# HMC1001_FreeSize_V1_0.net
KiCad netlist of a schematic drawn in Altium Designer
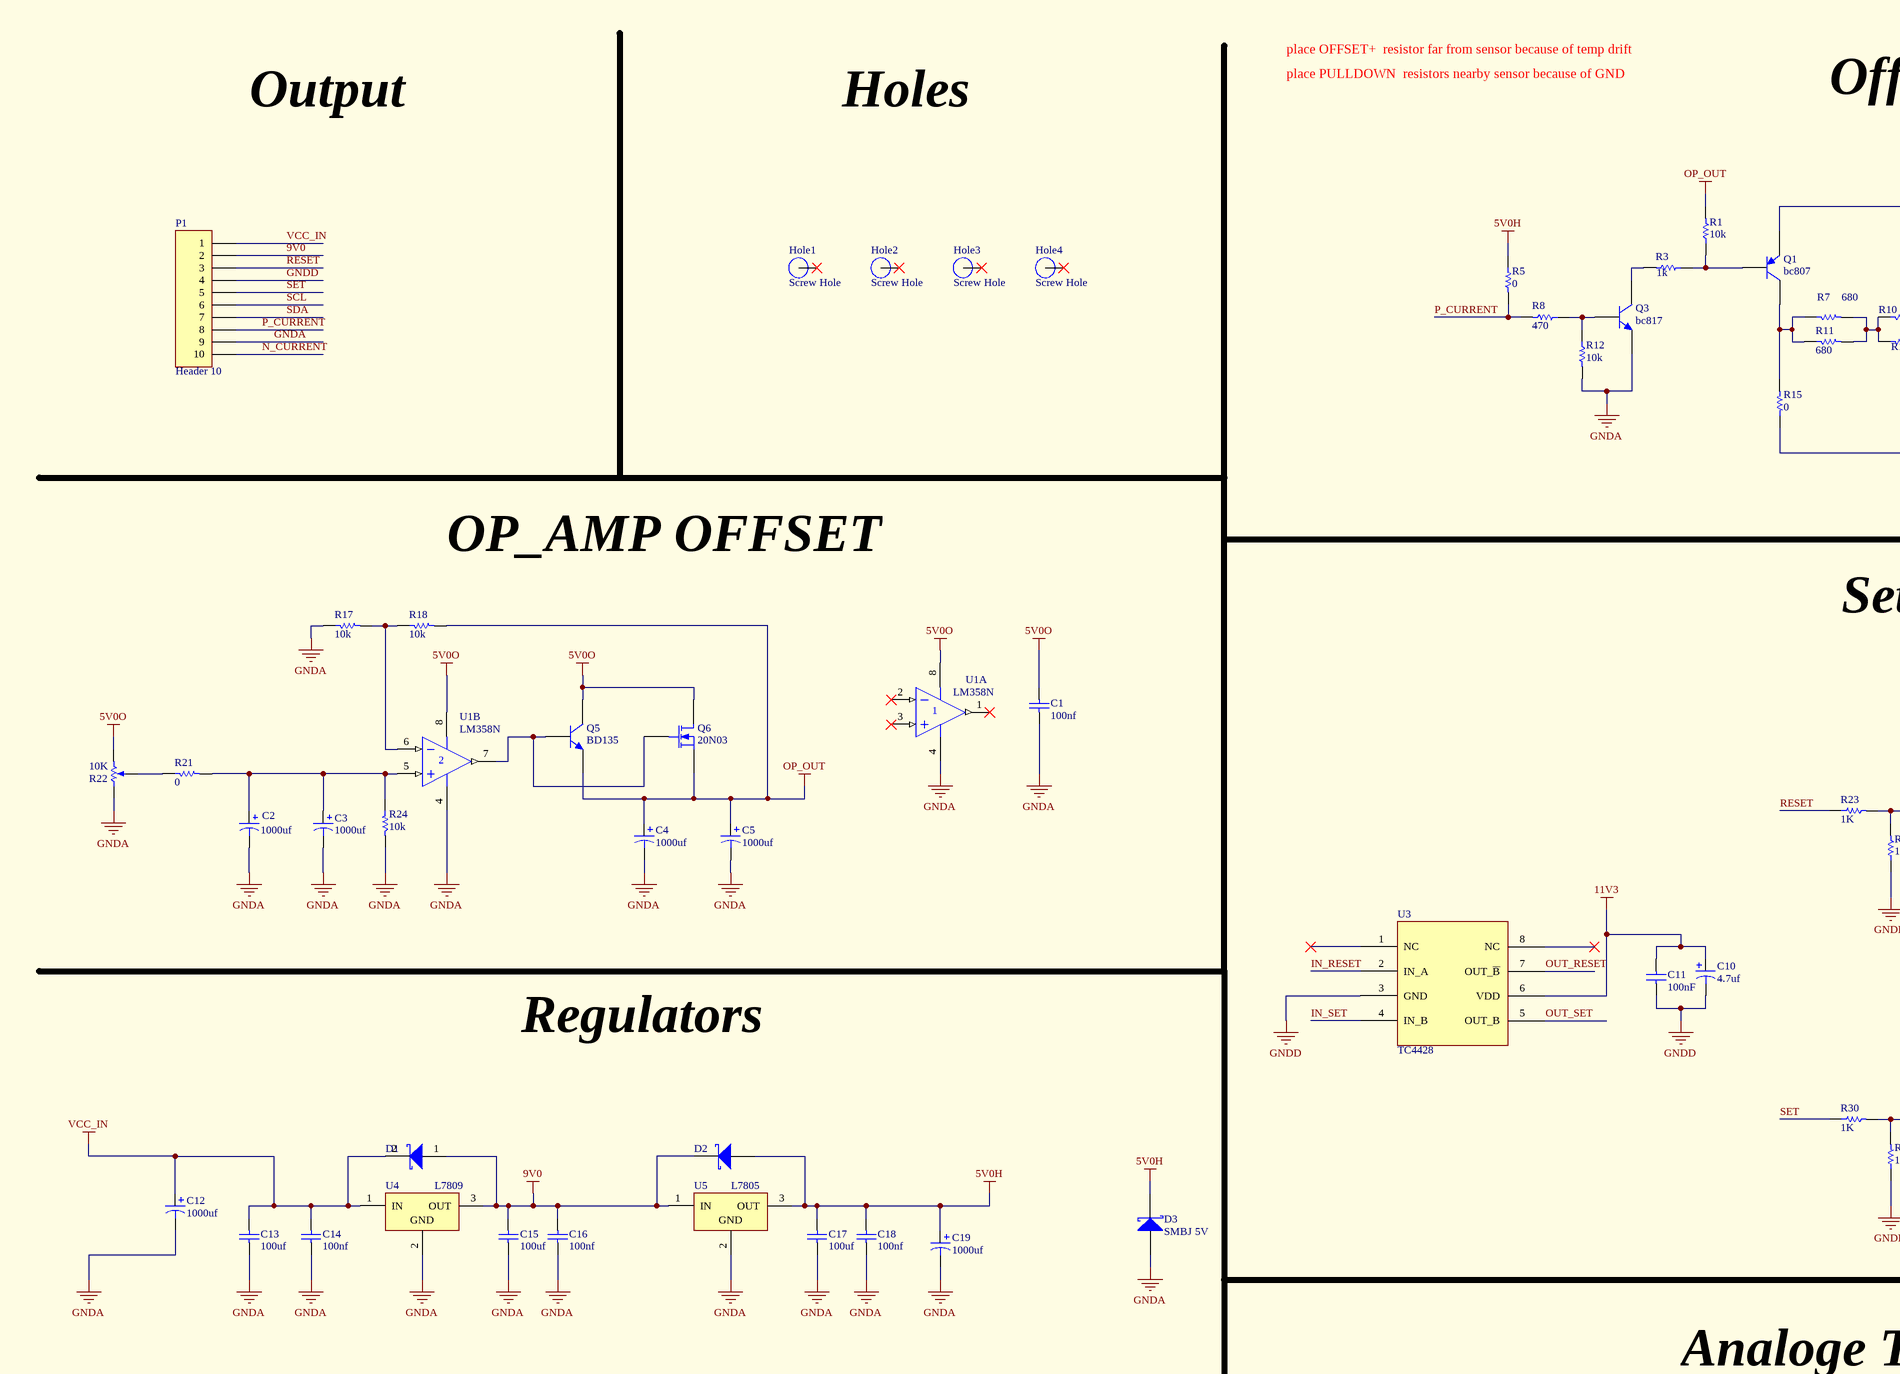
[diagram p0: HMC1001_FreeSize_V1_0.SchDoc, top left]
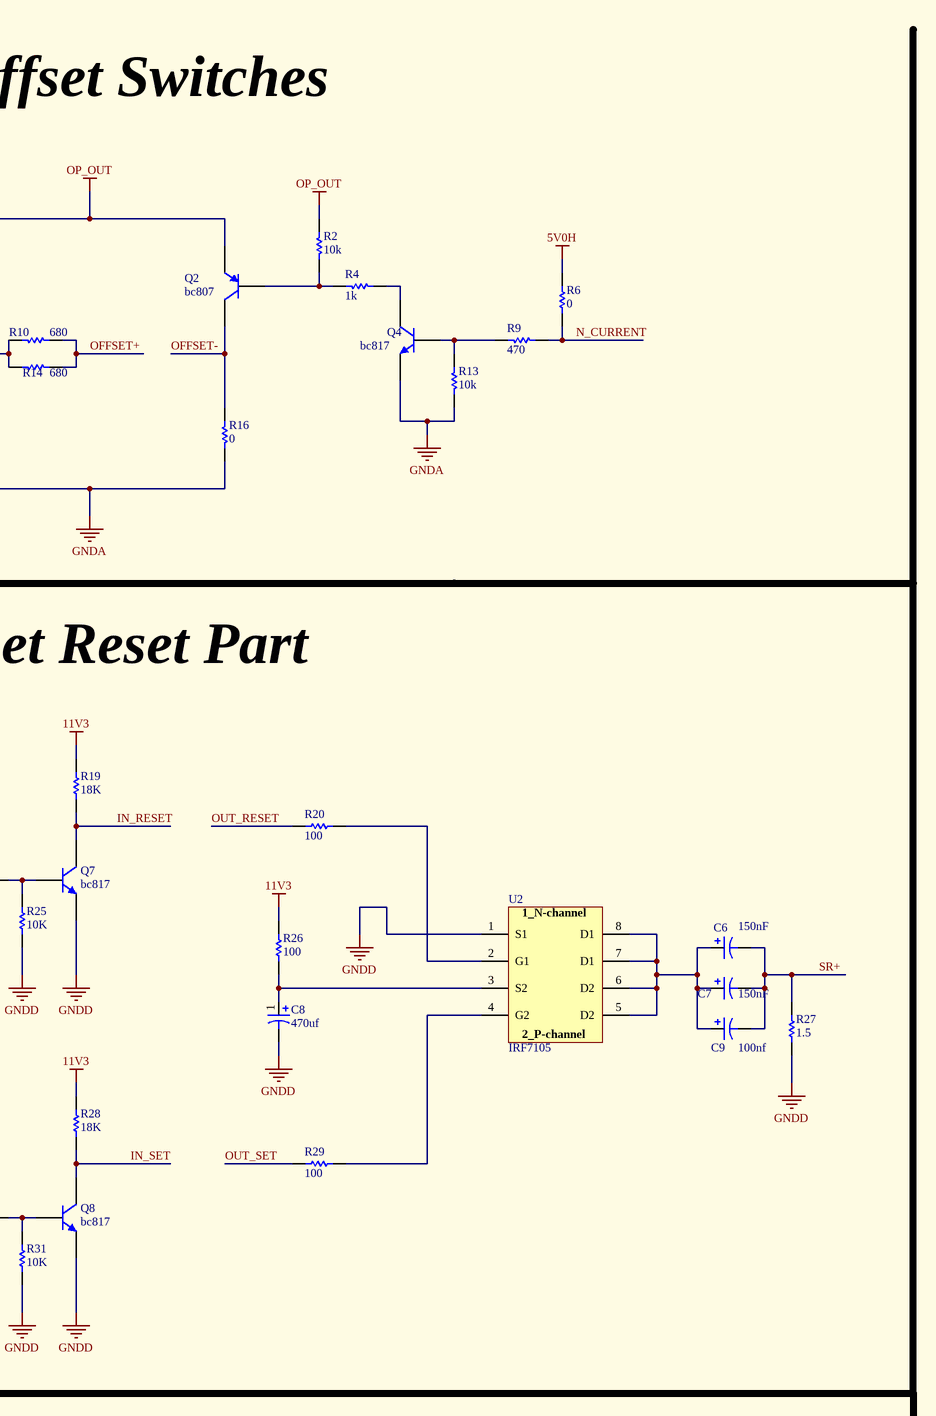
[diagram p1: HMC1001_FreeSize_V1_0.SchDoc, top right]
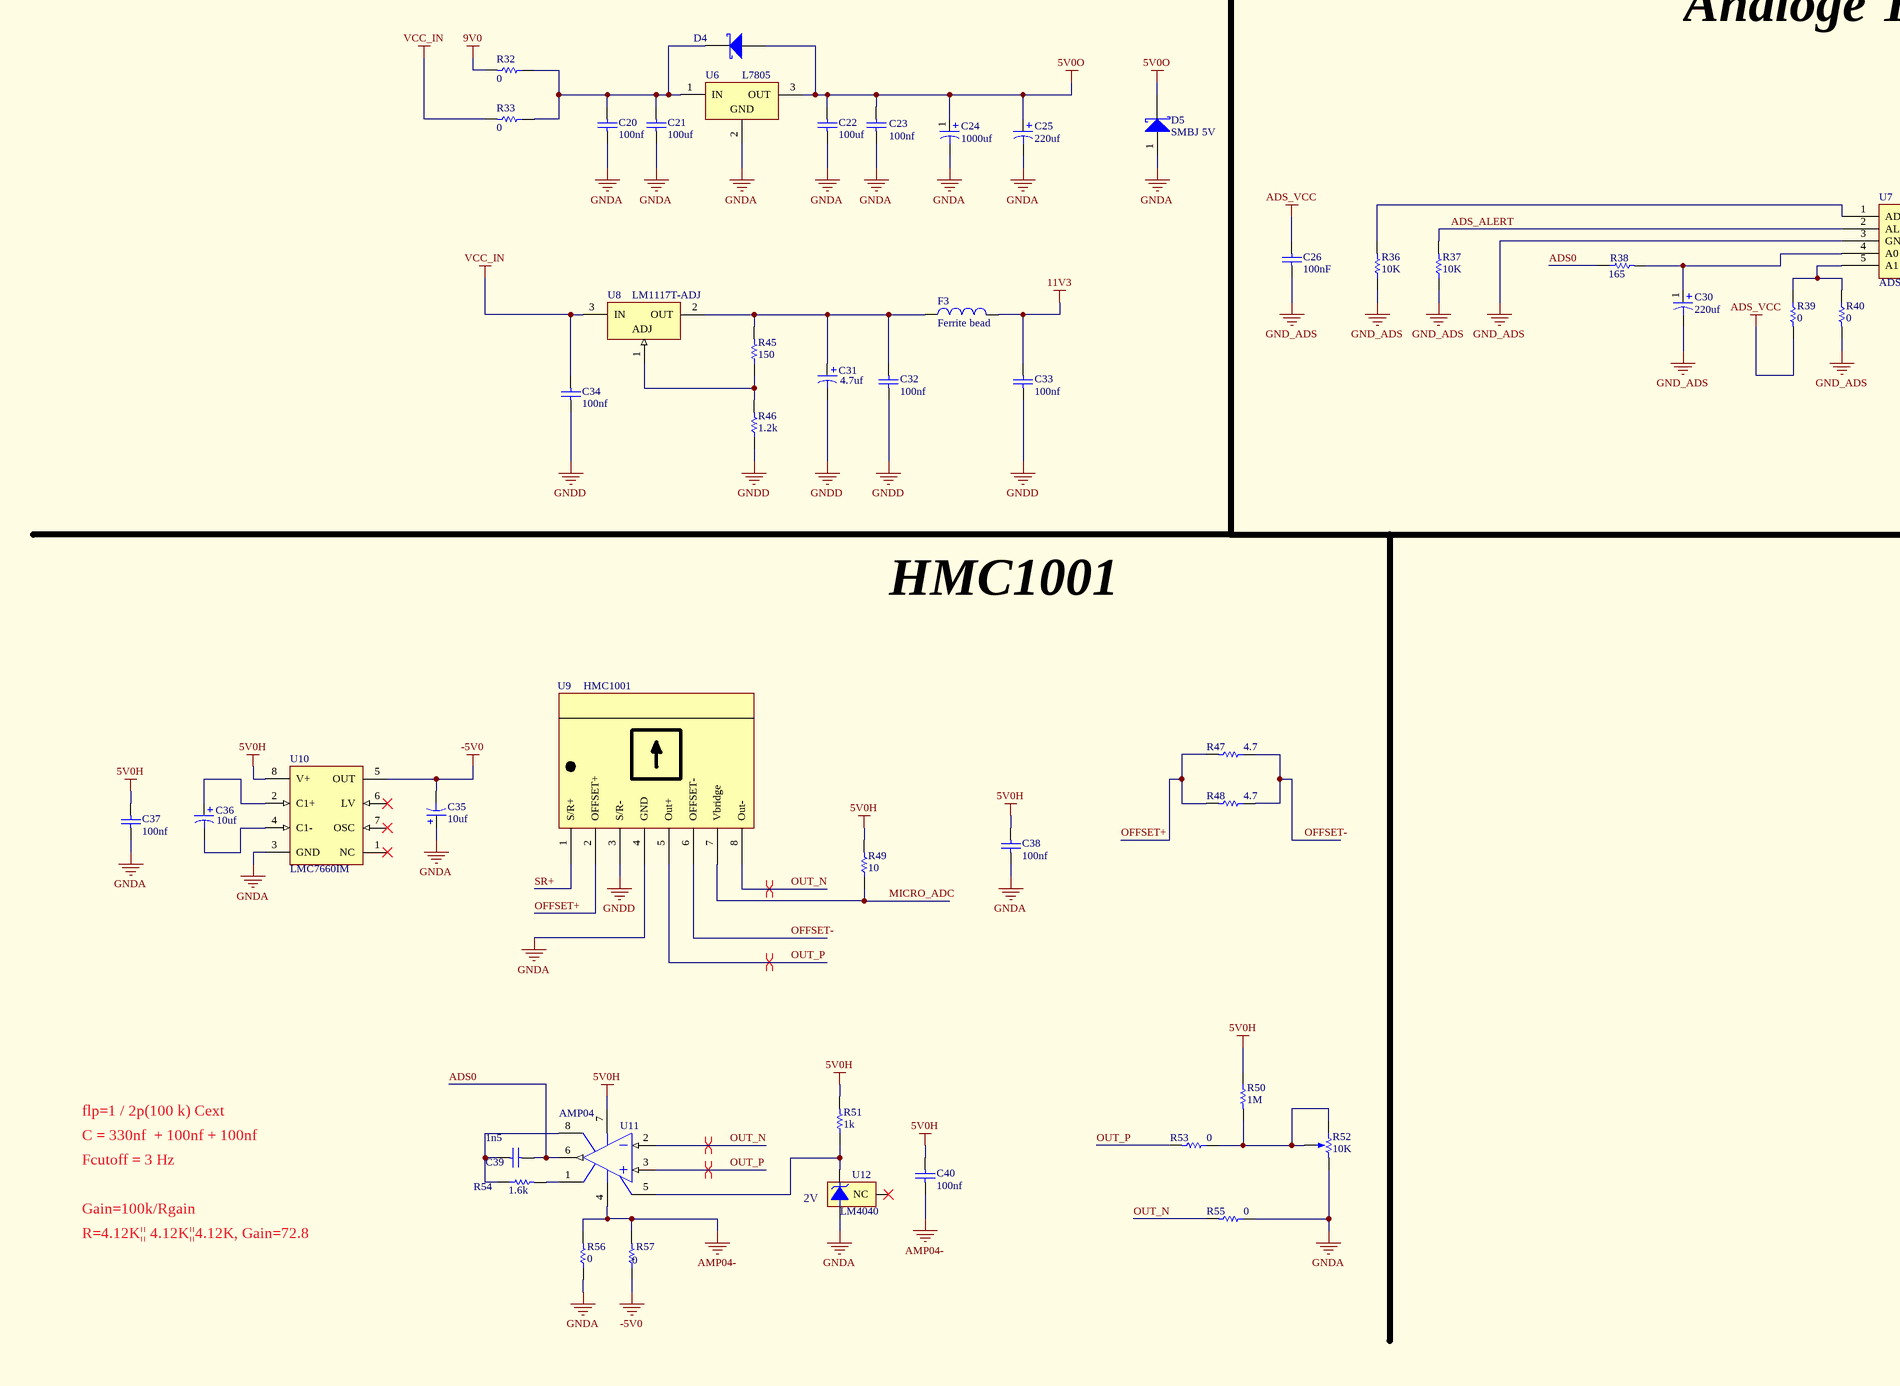
[diagram p2: HMC1001_FreeSize_V1_0.SchDoc, bottom left]
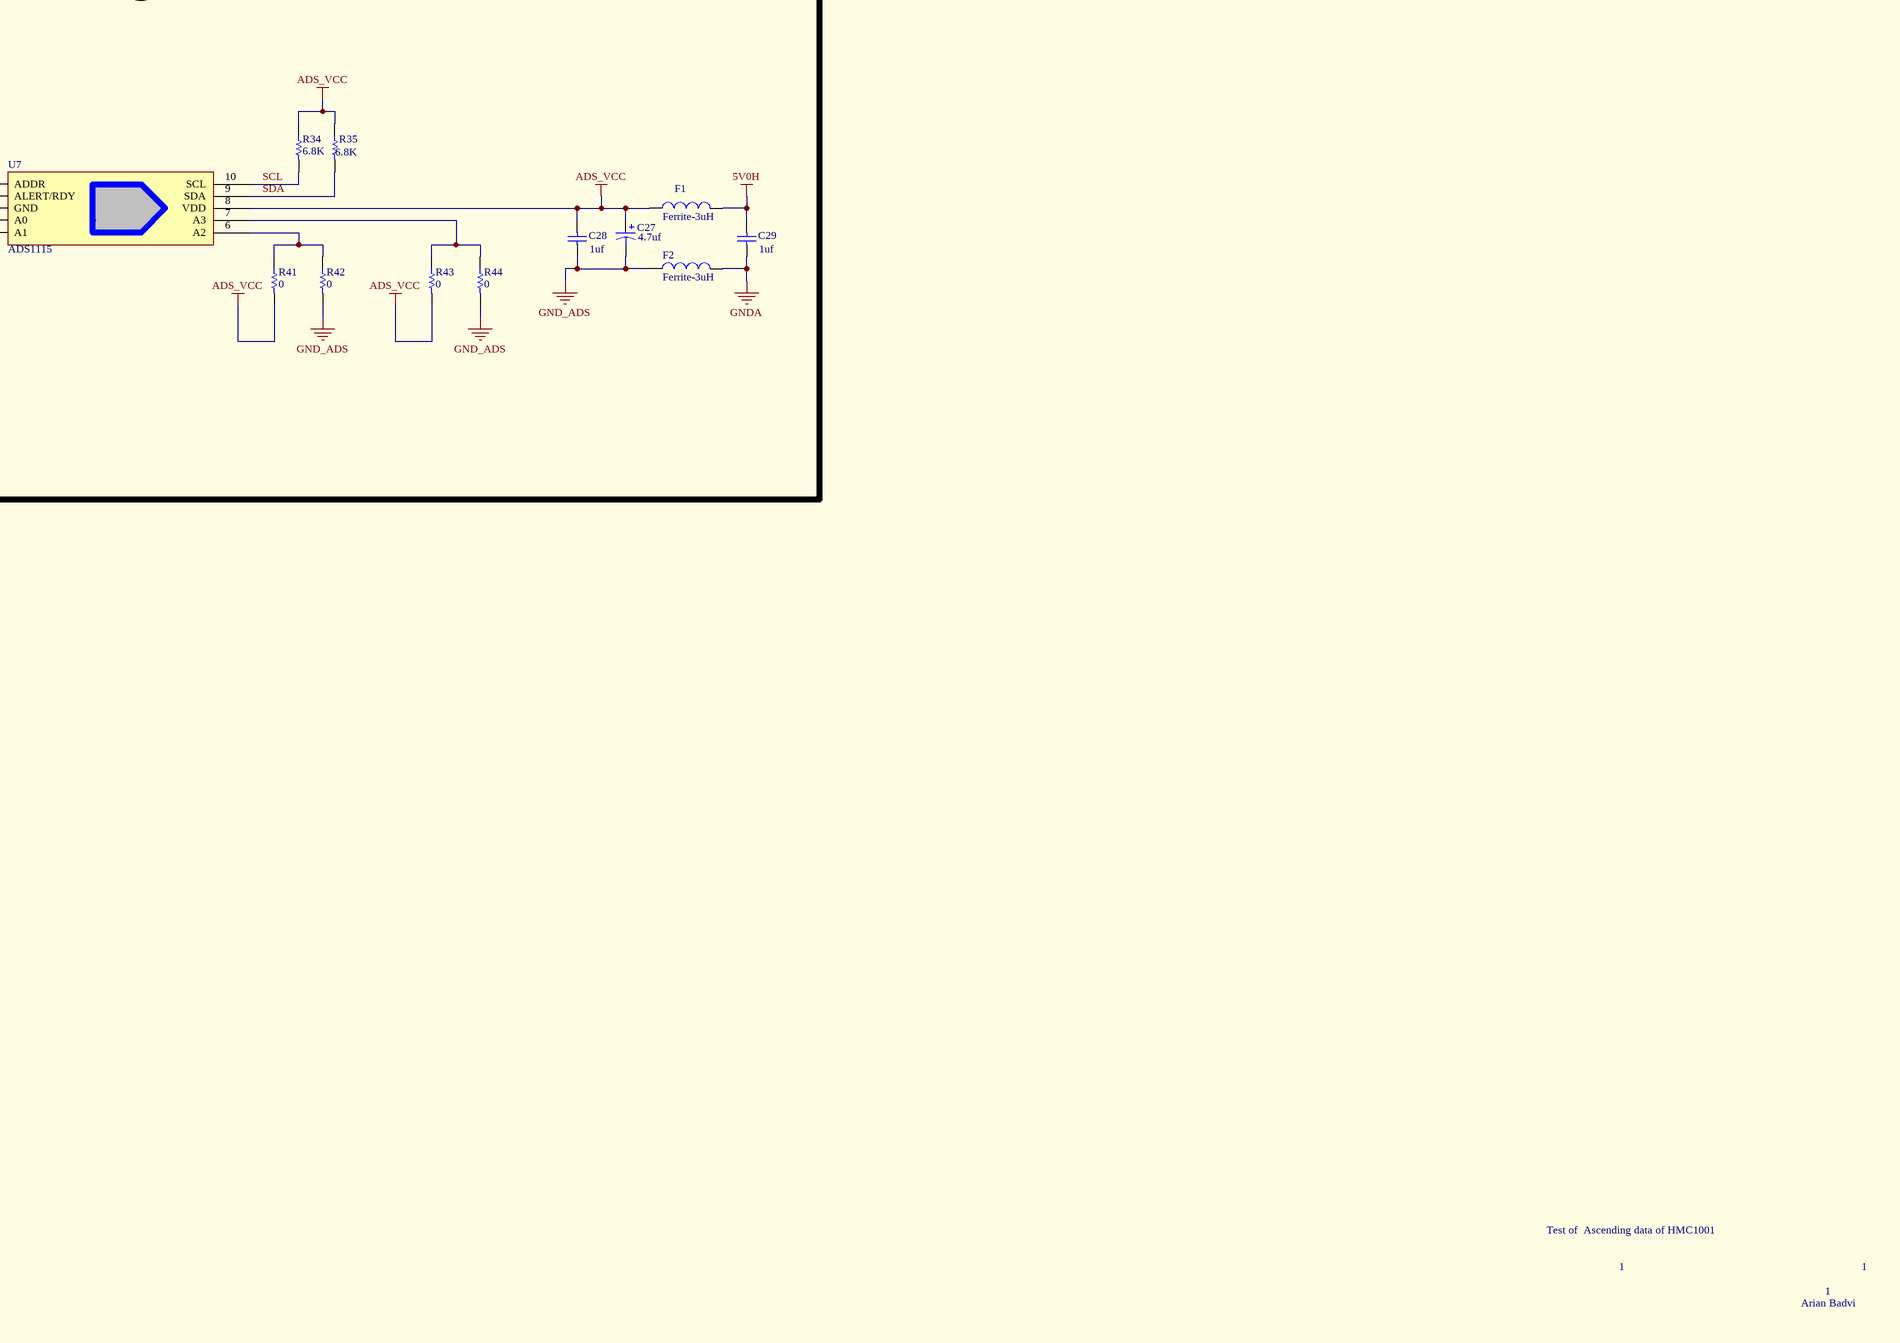
[diagram p3: HMC1001_FreeSize_V1_0.SchDoc, bottom right]

(export (version "E")
  (design (tool "Eeschema 10.0.6"))
  (components
    (comp (ref "C1")
      (value "100nf")
      (footprint "C_1206")
      (description "Capacitor")
      (fields (field (name "PUBLISHER") "Altium Limited"))
      (libsource (lib "Miscellaneous Devices") (part "Cap"))
    )
    (comp (ref "C2")
      (value "1000uf")
      (footprint "C_EL_10_10")
      (description "electrolytic smd cap 16V")
      (fields (field (name "PUBLISHER") "Altium Limited"))
      (libsource (lib "Miscellaneous Devices") (part "Cap Pol1"))
    )
    (comp (ref "C3")
      (value "1000uf")
      (footprint "C_EL_10_10")
      (description "electrolytic smd cap 16V")
      (fields (field (name "PUBLISHER") "Altium Limited"))
      (libsource (lib "Miscellaneous Devices") (part "Cap Pol1"))
    )
    (comp (ref "C4")
      (value "1000uf")
      (footprint "C_EL_10_10")
      (description "electrolytic smd cap 16V")
      (fields (field (name "PUBLISHER") "Altium Limited"))
      (libsource (lib "Miscellaneous Devices") (part "Cap Pol1"))
    )
    (comp (ref "C5")
      (value "1000uf")
      (footprint "C_EL_10_10")
      (description "electrolytic smd cap 16V")
      (fields (field (name "PUBLISHER") "Altium Limited"))
      (libsource (lib "Miscellaneous Devices") (part "Cap Pol1"))
    )
    (comp (ref "C6")
      (value "150nF")
      (footprint "cap_smd_a")
      (description "Polarized Capacitor (Radial)")
      (fields (field (name "PUBLISHER") "Altium Limited"))
      (libsource (lib "Miscellaneous Devices") (part "Cap Pol1"))
    )
    (comp (ref "C7")
      (value "150nF")
      (footprint "cap_smd_a")
      (description "Polarized Capacitor (Radial)")
      (fields (field (name "PUBLISHER") "Altium Limited"))
      (libsource (lib "Miscellaneous Devices") (part "Cap Pol1"))
    )
    (comp (ref "C8")
      (value "470uf")
      (footprint "cap_smd_d")
      (description "TAN CAP D SIZE")
      (fields (field (name "PUBLISHER") "Altium Limited"))
      (libsource (lib "") (part "Cap Pol1_1"))
    )
    (comp (ref "C9")
      (value "100nf")
      (footprint "cap_smd_a")
      (description "Polarized Capacitor (Radial)")
      (fields (field (name "PUBLISHER") "Altium Limited"))
      (libsource (lib "Miscellaneous Devices") (part "Cap Pol1"))
    )
    (comp (ref "C10")
      (value "4.7uf")
      (footprint "cap_smd_a")
      (description "Polarized Capacitor (Radial)")
      (fields (field (name "PUBLISHER") "Altium Limited"))
      (libsource (lib "") (part "Cap Pol1_2"))
    )
    (comp (ref "C11")
      (value "100nF")
      (footprint "C_1206")
      (description "Capacitor")
      (fields (field (name "PUBLISHER") "Altium Limited"))
      (libsource (lib "Miscellaneous Devices") (part "Cap"))
    )
    (comp (ref "C12")
      (value "1000uf")
      (footprint "C_EL_10_10")
      (description "electrolytic smd cap")
      (fields (field (name "PUBLISHER") "Altium Limited"))
      (libsource (lib "Miscellaneous Devices") (part "Cap Pol1"))
    )
    (comp (ref "C13")
      (value "100uf")
      (footprint "C_1206")
      (description "Capacitor, 1206")
      (fields (field (name "PUBLISHER") "Altium Limited"))
      (libsource (lib "Miscellaneous Devices") (part "Cap"))
    )
    (comp (ref "C14")
      (value "100nf")
      (footprint "C_1206")
      (description "Capacitor, 1206")
      (fields (field (name "PUBLISHER") "Altium Limited"))
      (libsource (lib "Miscellaneous Devices") (part "Cap"))
    )
    (comp (ref "C15")
      (value "100uf")
      (footprint "C_1206")
      (description "Capacitor, 1206")
      (fields (field (name "PUBLISHER") "Altium Limited"))
      (libsource (lib "Miscellaneous Devices") (part "Cap"))
    )
    (comp (ref "C16")
      (value "100nf")
      (footprint "C_1206")
      (description "Capacitor, 1206")
      (fields (field (name "PUBLISHER") "Altium Limited"))
      (libsource (lib "Miscellaneous Devices") (part "Cap"))
    )
    (comp (ref "C17")
      (value "100uf")
      (footprint "C_1206")
      (description "Capacitor, 1206")
      (fields (field (name "PUBLISHER") "Altium Limited"))
      (libsource (lib "Miscellaneous Devices") (part "Cap"))
    )
    (comp (ref "C18")
      (value "100nf")
      (footprint "C_1206")
      (description "Capacitor, 1206")
      (fields (field (name "PUBLISHER") "Altium Limited"))
      (libsource (lib "Miscellaneous Devices") (part "Cap"))
    )
    (comp (ref "C19")
      (value "1000uf")
      (footprint "C_EL_10_10")
      (description "electrolytic smd cap")
      (fields (field (name "PUBLISHER") "Altium Limited"))
      (libsource (lib "Miscellaneous Devices") (part "Cap Pol1"))
    )
    (comp (ref "C20")
      (value "100nf")
      (footprint "C_1206")
      (description "Capacitor, 1206")
      (fields (field (name "PUBLISHER") "Altium Limited"))
      (libsource (lib "Miscellaneous Devices") (part "Cap"))
    )
    (comp (ref "C21")
      (value "100uf")
      (footprint "C_1206")
      (description "Capacitor, 1206")
      (fields (field (name "PUBLISHER") "Altium Limited"))
      (libsource (lib "Miscellaneous Devices") (part "Cap"))
    )
    (comp (ref "C22")
      (value "100uf")
      (footprint "C_1206")
      (description "Capacitor, 1206")
      (fields (field (name "PUBLISHER") "Altium Limited"))
      (libsource (lib "Miscellaneous Devices") (part "Cap"))
    )
    (comp (ref "C23")
      (value "100nf")
      (footprint "C_1206")
      (description "Capacitor, 1206")
      (fields (field (name "PUBLISHER") "Altium Limited"))
      (libsource (lib "Miscellaneous Devices") (part "Cap"))
    )
    (comp (ref "C24")
      (value "1000uf")
      (footprint "C_EL_10_10")
      (description "electrolytic smd cap")
      (fields (field (name "PUBLISHER") "Altium Limited"))
      (libsource (lib "") (part "Cap Pol1_1"))
    )
    (comp (ref "C25")
      (value "220uf")
      (footprint "C_EL_6_6")
      (description "electrolytic smd cap 16V")
      (fields (field (name "PUBLISHER") "Altium Limited"))
      (libsource (lib "Miscellaneous Devices") (part "Cap Pol1"))
    )
    (comp (ref "C26")
      (value "100nF")
      (footprint "C_1206")
      (description "Capacitor")
      (fields (field (name "PUBLISHER") "Altium Limited"))
      (libsource (lib "Miscellaneous Devices") (part "Cap"))
    )
    (comp (ref "C27")
      (value "4.7uf")
      (footprint "CAP_SMD_A")
      (description "Tantalium Capacitor")
      (fields (field (name "PUBLISHER") "Altium Limited"))
      (libsource (lib "Library") (part "Cap Pol"))
    )
    (comp (ref "C28")
      (value "1uf")
      (footprint "C_1206")
      (description "Capacitor, 1206")
      (fields (field (name "PUBLISHER") "Altium Limited"))
      (libsource (lib "Library") (part "Cap"))
    )
    (comp (ref "C29")
      (value "1uf")
      (footprint "C_1206")
      (description "Capacitor, 1206")
      (fields (field (name "PUBLISHER") "Altium Limited"))
      (libsource (lib "Library") (part "Cap"))
    )
    (comp (ref "C30")
      (value "220uf")
      (footprint "cap_smd_d")
      (description "TAN CAP D SIZE")
      (fields (field (name "PUBLISHER") "Altium Limited"))
      (libsource (lib "") (part "Cap Pol1_1"))
    )
    (comp (ref "C31")
      (value "4.7uf")
      (footprint "cap_smd_a")
      (description "Polarized Capacitor (Radial)")
      (fields (field (name "PUBLISHER") "Altium Limited"))
      (libsource (lib "Miscellaneous Devices") (part "Cap Pol1"))
    )
    (comp (ref "C32")
      (value "100nf")
      (footprint "C_1206")
      (description "Capacitor")
      (fields (field (name "PUBLISHER") "Altium Limited"))
      (libsource (lib "Miscellaneous Devices") (part "Cap"))
    )
    (comp (ref "C33")
      (value "100nf")
      (footprint "C_1206")
      (description "Capacitor")
      (fields (field (name "PUBLISHER") "Altium Limited"))
      (libsource (lib "Miscellaneous Devices") (part "Cap"))
    )
    (comp (ref "C34")
      (value "100nf")
      (footprint "C_1206")
      (description "Capacitor")
      (fields (field (name "PUBLISHER") "Altium Limited"))
      (libsource (lib "Miscellaneous Devices") (part "Cap"))
    )
    (comp (ref "C35")
      (value "10uf")
      (footprint "cap_smd_a")
      (description "Polarized Capacitor (Radial)")
      (fields (field (name "PUBLISHER") "Altium Limited"))
      (libsource (lib "Miscellaneous Devices") (part "Cap Pol1"))
    )
    (comp (ref "C36")
      (value "10uf")
      (footprint "cap_smd_a")
      (description "Polarized Capacitor (Radial)")
      (fields (field (name "PUBLISHER") "Altium Limited"))
      (libsource (lib "Miscellaneous Devices") (part "Cap Pol1"))
    )
    (comp (ref "C37")
      (value "100nf")
      (footprint "C_1206")
      (description "Capacitor")
      (fields (field (name "PUBLISHER") "Altium Limited"))
      (libsource (lib "Miscellaneous Devices") (part "Cap"))
    )
    (comp (ref "C38")
      (value "100nf")
      (footprint "C_1206")
      (description "Capacitor")
      (fields (field (name "PUBLISHER") "Altium Limited"))
      (libsource (lib "Miscellaneous Devices") (part "Cap"))
    )
    (comp (ref "C39")
      (value "1n5")
      (footprint "C_1206")
      (description "Capacitor")
      (fields (field (name "PUBLISHER") "Altium Limited"))
      (libsource (lib "Library") (part "Cap"))
    )
    (comp (ref "C40")
      (value "100nf")
      (footprint "C_1206")
      (description "Capacitor")
      (fields (field (name "PUBLISHER") "Altium Limited"))
      (libsource (lib "Miscellaneous Devices") (part "Cap"))
    )
    (comp (ref "D1")
      (value "D Schottky")
      (footprint "ZENER")
      (description "Schottky Diode, 1N4148")
      (fields (field (name "PUBLISHER") "Altium Limited"))
      (libsource (lib "Miscellaneous Devices") (part "D Schottky"))
    )
    (comp (ref "D2")
      (value "D Schottky")
      (footprint "ZENER")
      (description "Schottky Diode, 1N4148")
      (fields (field (name "PUBLISHER") "Altium Limited"))
      (libsource (lib "") (part "D Schottky_1"))
    )
    (comp (ref "D3")
      (value "SMBJ 5V")
      (footprint "TVS")
      (description "Schottky Rectifier")
      (fields (field (name "PUBLISHER") "Altium Limited"))
      (libsource (lib "") (part "Diode 18TQ045_1"))
    )
    (comp (ref "D4")
      (value "D Schottky")
      (footprint "ZENER")
      (description "Schottky Diode, 1N4148")
      (fields (field (name "PUBLISHER") "Altium Limited"))
      (libsource (lib "") (part "D Schottky_1"))
    )
    (comp (ref "D5")
      (value "SMBJ 5V")
      (footprint "TVS")
      (description "Schottky Rectifier")
      (fields (field (name "PUBLISHER") "Altium Limited"))
      (libsource (lib "Miscellaneous Devices") (part "Diode 18TQ045"))
    )
    (comp (ref "F1")
      (value "Ferrite-3uH")
      (footprint "1206")
      (description "Inductor")
      (fields (field (name "PUBLISHER") "Altium Limited"))
      (libsource (lib "Miscellaneous Devices") (part "Inductor"))
    )
    (comp (ref "F2")
      (value "Ferrite-3uH")
      (footprint "1206")
      (description "Inductor")
      (fields (field (name "PUBLISHER") "Altium Limited"))
      (libsource (lib "Miscellaneous Devices") (part "Inductor"))
    )
    (comp (ref "F3")
      (value "Ferrite bead")
      (footprint "1206")
      (description "Ferrite bead, 1206")
      (fields (field (name "PUBLISHER") "Altium Limited"))
      (libsource (lib "Miscellaneous Devices") (part "Inductor"))
    )
    (comp (ref "Hole1")
      (value "Screw Hole")
      (footprint "HOLE_3mm_5mm")
      (libsource (lib "Sajad_Altium_Library") (part "Screw Hole"))
    )
    (comp (ref "Hole2")
      (value "Screw Hole")
      (footprint "HOLE_3mm_5mm")
      (libsource (lib "Sajad_Altium_Library") (part "Screw Hole"))
    )
    (comp (ref "Hole3")
      (value "Screw Hole")
      (footprint "HOLE_3mm_5mm")
      (libsource (lib "Sajad_Altium_Library") (part "Screw Hole"))
    )
    (comp (ref "Hole4")
      (value "Screw Hole")
      (footprint "HOLE_3mm_5mm")
      (libsource (lib "Sajad_Altium_Library") (part "Screw Hole"))
    )
    (comp (ref "P1")
      (value "Header 10")
      (footprint "HDR_F_1X10")
      (description "Header, 10-Pin")
      (fields (field (name "PUBLISHER") "Altium Limited"))
      (libsource (lib "Miscellaneous Connectors") (part "Header 10"))
    )
    (comp (ref "Q1")
      (value "bc807")
      (footprint "sot-23")
      (description "PNP General Purpose Amplifier")
      (fields (field (name "PUBLISHER") "Altium Limited"))
      (libsource (lib "Miscellaneous Devices") (part "2N3906"))
    )
    (comp (ref "Q2")
      (value "bc807")
      (footprint "sot-23")
      (description "PNP General Purpose Amplifier")
      (fields (field (name "PUBLISHER") "Altium Limited"))
      (libsource (lib "Miscellaneous Devices") (part "2N3906"))
    )
    (comp (ref "Q3")
      (value "bc817")
      (footprint "sot-23")
      (description "NPN General Purpose Amplifier")
      (fields (field (name "PUBLISHER") "Altium Limited"))
      (libsource (lib "Miscellaneous Devices") (part "2N3904"))
    )
    (comp (ref "Q4")
      (value "bc817")
      (footprint "sot-23")
      (description "NPN General Purpose Amplifier")
      (fields (field (name "PUBLISHER") "Altium Limited"))
      (libsource (lib "Miscellaneous Devices") (part "2N3904"))
    )
    (comp (ref "Q5")
      (value "BD135")
      (footprint "sot-32")
      (description "NPN General Purpose Amplifier")
      (fields (field (name "PUBLISHER") "Altium Limited"))
      (libsource (lib "") (part "2N3904_1"))
    )
    (comp (ref "Q6")
      (value "20N03")
      (footprint "dpak")
      (description "N-Channel MOSFET")
      (fields (field (name "PUBLISHER") "Altium Limited"))
      (libsource (lib "Miscellaneous Devices") (part "MOSFET-N"))
    )
    (comp (ref "Q7")
      (value "bc817")
      (footprint "sot-23")
      (description "NPN General Purpose Amplifier")
      (fields (field (name "PUBLISHER") "Altium Limited"))
      (libsource (lib "Miscellaneous Devices") (part "2N3904"))
    )
    (comp (ref "Q8")
      (value "bc817")
      (footprint "sot-23")
      (description "NPN General Purpose Amplifier")
      (fields (field (name "PUBLISHER") "Altium Limited"))
      (libsource (lib "Miscellaneous Devices") (part "2N3904"))
    )
    (comp (ref "R1")
      (value "10k")
      (footprint "1206")
      (description "Resistor")
      (fields (field (name "PUBLISHER") "Altium Limited"))
      (libsource (lib "Miscellaneous Devices") (part "Res1"))
    )
    (comp (ref "R2")
      (value "10k")
      (footprint "1206")
      (description "Resistor")
      (fields (field (name "PUBLISHER") "Altium Limited"))
      (libsource (lib "Miscellaneous Devices") (part "Res1"))
    )
    (comp (ref "R3")
      (value "1k")
      (footprint "1206")
      (description "Resistor")
      (fields (field (name "PUBLISHER") "Altium Limited"))
      (libsource (lib "Miscellaneous Devices") (part "Res1"))
    )
    (comp (ref "R4")
      (value "1k")
      (footprint "1206")
      (description "Resistor")
      (fields (field (name "PUBLISHER") "Altium Limited"))
      (libsource (lib "Miscellaneous Devices") (part "Res1"))
    )
    (comp (ref "R5")
      (value "0")
      (footprint "1206")
      (description "Resistor")
      (fields (field (name "PUBLISHER") "Altium Limited"))
      (libsource (lib "Miscellaneous Devices") (part "Res1"))
    )
    (comp (ref "R6")
      (value "0")
      (footprint "1206")
      (description "Resistor")
      (fields (field (name "PUBLISHER") "Altium Limited"))
      (libsource (lib "Miscellaneous Devices") (part "Res1"))
    )
    (comp (ref "R7")
      (value "680")
      (footprint "R2W_AX_VER")
      (description "Resistor")
      (fields (field (name "PUBLISHER") "Altium Limited"))
      (libsource (lib "Miscellaneous Devices") (part "Res1"))
    )
    (comp (ref "R8")
      (value "470")
      (footprint "1206")
      (description "Resistor")
      (fields (field (name "PUBLISHER") "Altium Limited"))
      (libsource (lib "Miscellaneous Devices") (part "Res1"))
    )
    (comp (ref "R9")
      (value "470")
      (footprint "1206")
      (description "Resistor")
      (fields (field (name "PUBLISHER") "Altium Limited"))
      (libsource (lib "Miscellaneous Devices") (part "Res1"))
    )
    (comp (ref "R10")
      (value "680")
      (footprint "R2W_AX_VER")
      (description "Resistor")
      (fields (field (name "PUBLISHER") "Altium Limited"))
      (libsource (lib "Miscellaneous Devices") (part "Res1"))
    )
    (comp (ref "R11")
      (value "680")
      (footprint "R2W_AX_VER")
      (description "Resistor")
      (fields (field (name "PUBLISHER") "Altium Limited"))
      (libsource (lib "Miscellaneous Devices") (part "Res1"))
    )
    (comp (ref "R12")
      (value "10k")
      (footprint "1206")
      (description "Resistor")
      (fields (field (name "PUBLISHER") "Altium Limited"))
      (libsource (lib "Miscellaneous Devices") (part "Res1"))
    )
    (comp (ref "R13")
      (value "10k")
      (footprint "1206")
      (description "Resistor")
      (fields (field (name "PUBLISHER") "Altium Limited"))
      (libsource (lib "Miscellaneous Devices") (part "Res1"))
    )
    (comp (ref "R14")
      (value "680")
      (footprint "R2W_AX_VER")
      (description "Resistor")
      (fields (field (name "PUBLISHER") "Altium Limited"))
      (libsource (lib "Miscellaneous Devices") (part "Res1"))
    )
    (comp (ref "R15")
      (value "0")
      (footprint "0603")
      (description "Resistor")
      (fields (field (name "PUBLISHER") "Altium Limited"))
      (libsource (lib "") (part "Res1_1"))
    )
    (comp (ref "R16")
      (value "0")
      (footprint "0603")
      (description "Resistor")
      (fields (field (name "PUBLISHER") "Altium Limited"))
      (libsource (lib "") (part "Res1_1"))
    )
    (comp (ref "R17")
      (value "10k")
      (footprint "1206")
      (description "Resistor")
      (fields (field (name "PUBLISHER") "Altium Limited"))
      (libsource (lib "") (part "Res1_1"))
    )
    (comp (ref "R18")
      (value "10k")
      (footprint "1206")
      (description "Resistor")
      (fields (field (name "PUBLISHER") "Altium Limited"))
      (libsource (lib "") (part "Res1_1"))
    )
    (comp (ref "R19")
      (value "18K")
      (footprint "1206")
      (description "Resistor")
      (fields (field (name "PUBLISHER") "Altium Limited"))
      (libsource (lib "Miscellaneous Devices") (part "Res1"))
    )
    (comp (ref "R20")
      (value "100")
      (footprint "0603")
      (description "Resistor")
      (fields (field (name "PUBLISHER") "Altium Limited"))
      (libsource (lib "Miscellaneous Devices") (part "Res1"))
    )
    (comp (ref "R21")
      (value "0")
      (footprint "1206")
      (description "Resistor")
      (fields (field (name "PUBLISHER") "Altium Limited"))
      (libsource (lib "") (part "Res1_1"))
    )
    (comp (ref "R22")
      (value "10K")
      (footprint "POT_3296w")
      (description "Potentiometer")
      (fields (field (name "Comment") "RPot") (field (name "PUBLISHER") "Altium Limited"))
      (libsource (lib "Miscellaneous Devices") (part "RPot"))
    )
    (comp (ref "R23")
      (value "1K")
      (footprint "1206")
      (description "Resistor")
      (fields (field (name "PUBLISHER") "Altium Limited"))
      (libsource (lib "Miscellaneous Devices") (part "Res1"))
    )
    (comp (ref "R24")
      (value "10k")
      (footprint "1206")
      (description "Resistor")
      (fields (field (name "PUBLISHER") "Altium Limited"))
      (libsource (lib "Miscellaneous Devices") (part "Res1"))
    )
    (comp (ref "R25")
      (value "10K")
      (footprint "1206")
      (description "Resistor")
      (fields (field (name "PUBLISHER") "Altium Limited"))
      (libsource (lib "Miscellaneous Devices") (part "Res1"))
    )
    (comp (ref "R26")
      (value "100")
      (footprint "1206")
      (description "Resistor")
      (fields (field (name "PUBLISHER") "Altium Limited"))
      (libsource (lib "Miscellaneous Devices") (part "Res1"))
    )
    (comp (ref "R27")
      (value "1.5")
      (footprint "1206")
      (description "Resistor")
      (fields (field (name "PUBLISHER") "Altium Limited"))
      (libsource (lib "Miscellaneous Devices") (part "Res1"))
    )
    (comp (ref "R28")
      (value "18K")
      (footprint "1206")
      (description "Resistor")
      (fields (field (name "PUBLISHER") "Altium Limited"))
      (libsource (lib "Miscellaneous Devices") (part "Res1"))
    )
    (comp (ref "R29")
      (value "100")
      (footprint "0603")
      (description "Resistor")
      (fields (field (name "PUBLISHER") "Altium Limited"))
      (libsource (lib "Miscellaneous Devices") (part "Res1"))
    )
    (comp (ref "R30")
      (value "1K")
      (footprint "1206")
      (description "Resistor")
      (fields (field (name "PUBLISHER") "Altium Limited"))
      (libsource (lib "Miscellaneous Devices") (part "Res1"))
    )
    (comp (ref "R31")
      (value "10K")
      (footprint "1206")
      (description "Resistor")
      (fields (field (name "PUBLISHER") "Altium Limited"))
      (libsource (lib "Miscellaneous Devices") (part "Res1"))
    )
    (comp (ref "R32")
      (value "0")
      (footprint "0603")
      (description "Resistor")
      (fields (field (name "PUBLISHER") "Seyed Razi Vesali") (field (name "EMAIL") "razi.vesali@gmail.com"))
      (libsource (lib "resistor1") (part "Resistor"))
    )
    (comp (ref "R33")
      (value "0")
      (footprint "0603")
      (description "Resistor")
      (fields (field (name "PUBLISHER") "Seyed Razi Vesali") (field (name "EMAIL") "razi.vesali@gmail.com"))
      (libsource (lib "resistor1") (part "Resistor"))
    )
    (comp (ref "R34")
      (value "6.8K")
      (footprint "1206")
      (description "General Resistor")
      (fields (field (name "PUBLISHER") "Altium Limited"))
      (libsource (lib "Library") (part "Resistor"))
    )
    (comp (ref "R35")
      (value "6.8K")
      (footprint "1206")
      (description "General Resistor")
      (fields (field (name "PUBLISHER") "Altium Limited"))
      (libsource (lib "Library") (part "Resistor"))
    )
    (comp (ref "R36")
      (value "10K")
      (footprint "1206")
      (description "General Resistor")
      (fields (field (name "PUBLISHER") "Altium Limited"))
      (libsource (lib "Library") (part "Resistor"))
    )
    (comp (ref "R37")
      (value "10K")
      (footprint "1206")
      (description "General Resistor")
      (fields (field (name "PUBLISHER") "Altium Limited"))
      (libsource (lib "Library") (part "Resistor"))
    )
    (comp (ref "R38")
      (value "165")
      (footprint "1206")
      (description "General Resistor")
      (fields (field (name "PUBLISHER") "Altium Limited"))
      (libsource (lib "Library") (part "Resistor"))
    )
    (comp (ref "R39")
      (value "0")
      (footprint "1206")
      (description "General Resistor")
      (fields (field (name "PUBLISHER") "Altium Limited"))
      (libsource (lib "Library") (part "Resistor"))
    )
    (comp (ref "R40")
      (value "0")
      (footprint "1206")
      (description "General Resistor")
      (fields (field (name "PUBLISHER") "Altium Limited"))
      (libsource (lib "Library") (part "Resistor"))
    )
    (comp (ref "R41")
      (value "0")
      (footprint "1206")
      (description "General Resistor")
      (fields (field (name "PUBLISHER") "Altium Limited"))
      (libsource (lib "Library") (part "Resistor"))
    )
    (comp (ref "R42")
      (value "0")
      (footprint "1206")
      (description "General Resistor")
      (fields (field (name "PUBLISHER") "Altium Limited"))
      (libsource (lib "Library") (part "Resistor"))
    )
    (comp (ref "R43")
      (value "0")
      (footprint "1206")
      (description "General Resistor")
      (fields (field (name "PUBLISHER") "Altium Limited"))
      (libsource (lib "Library") (part "Resistor"))
    )
    (comp (ref "R44")
      (value "0")
      (footprint "1206")
      (description "General Resistor")
      (fields (field (name "PUBLISHER") "Altium Limited"))
      (libsource (lib "Library") (part "Resistor"))
    )
    (comp (ref "R45")
      (value "150")
      (footprint "1206")
      (description "Resistor")
      (fields (field (name "PUBLISHER") "Seyed Razi Vesali") (field (name "EMAIL") "razi.vesali@gmail.com"))
      (libsource (lib "resistor1") (part "Resistor"))
    )
    (comp (ref "R46")
      (value "1.2k")
      (footprint "1206")
      (description "Resistor")
      (fields (field (name "PUBLISHER") "Seyed Razi Vesali") (field (name "EMAIL") "razi.vesali@gmail.com"))
      (libsource (lib "resistor1") (part "Resistor"))
    )
    (comp (ref "R47")
      (value "4.7")
      (footprint "R025W_AX04")
      (description "Resistor")
      (fields (field (name "PUBLISHER") "Seyed Razi Vesali") (field (name "EMAIL") "razi.vesali@gmail.com"))
      (libsource (lib "resistor1") (part "Resistor"))
    )
    (comp (ref "R48")
      (value "4.7")
      (footprint "R025W_AX04")
      (description "Resistor")
      (fields (field (name "PUBLISHER") "Seyed Razi Vesali") (field (name "EMAIL") "razi.vesali@gmail.com"))
      (libsource (lib "resistor1") (part "Resistor"))
    )
    (comp (ref "R49")
      (value "10")
      (footprint "1206")
      (description "Resistor")
      (fields (field (name "PUBLISHER") "Seyed Razi Vesali") (field (name "EMAIL") "razi.vesali@gmail.com"))
      (libsource (lib "resistor1") (part "Resistor"))
    )
    (comp (ref "R50")
      (value "1M")
      (footprint "R025W_AX04")
      (description "Resistor")
      (fields (field (name "PUBLISHER") "Seyed Razi Vesali") (field (name "EMAIL") "razi.vesali@gmail.com"))
      (libsource (lib "resistor1") (part "Resistor"))
    )
    (comp (ref "R51")
      (value "1k")
      (footprint "1206")
      (description "Resistor")
      (fields (field (name "PUBLISHER") "Seyed Razi Vesali") (field (name "EMAIL") "razi.vesali@gmail.com"))
      (libsource (lib "resistor1") (part "Resistor"))
    )
    (comp (ref "R52")
      (value "10K")
      (footprint "POT_3296w")
      (description "Potentiometer")
      (fields (field (name "Comment") "RPot") (field (name "PUBLISHER") "Altium Limited"))
      (libsource (lib "Miscellaneous Devices") (part "RPot"))
    )
    (comp (ref "R53")
      (value "0")
      (footprint "0603")
      (description "Resistor")
      (fields (field (name "PUBLISHER") "Seyed Razi Vesali") (field (name "EMAIL") "razi.vesali@gmail.com"))
      (libsource (lib "resistor1") (part "Resistor"))
    )
    (comp (ref "R54")
      (value "1.6k")
      (footprint "1206")
      (description "General Resistor")
      (fields (field (name "PUBLISHER") "Altium Limited"))
      (libsource (lib "Library") (part "Resistor"))
    )
    (comp (ref "R55")
      (value "0")
      (footprint "0603")
      (description "Resistor")
      (fields (field (name "PUBLISHER") "Seyed Razi Vesali") (field (name "EMAIL") "razi.vesali@gmail.com"))
      (libsource (lib "resistor1") (part "Resistor"))
    )
    (comp (ref "R56")
      (value "0")
      (footprint "0603")
      (description "Resistor")
      (fields (field (name "PUBLISHER") "Seyed Razi Vesali") (field (name "EMAIL") "razi.vesali@gmail.com"))
      (libsource (lib "resistor1") (part "Resistor"))
    )
    (comp (ref "R57")
      (value "0")
      (footprint "0603")
      (description "Resistor")
      (fields (field (name "PUBLISHER") "Seyed Razi Vesali") (field (name "EMAIL") "razi.vesali@gmail.com"))
      (libsource (lib "resistor1") (part "Resistor"))
    )
    (comp (ref "U1")
      (value "LM358N")
      (footprint "sop8")
      (description "Dual Low-Power Operational Amplifier")
      (fields (field (name "PUBLISHER") "Altium Limited"))
      (libsource (lib "Motorola Amplifier Operational Amplifier") (part "LM358N"))
    )
    (comp (ref "U2") (value "IRF7105") (footprint "sop8") (libsource (lib "irf7106") (part "IRF7106")))
    (comp (ref "U3") (value "TC4428") (footprint "sop8") (libsource (lib "tc4428") (part "TC4428")))
    (comp (ref "U4")
      (value "L7809")
      (footprint "TO220")
      (description "Positive Voltage Regulator")
      (fields (field (name "PUBLISHER") "Altium Limited"))
      (libsource (lib "ST Power Mgt Voltage Regulator") (part "L7805CD2T"))
    )
    (comp (ref "U5")
      (value "L7805")
      (footprint "TO220")
      (description "Positive Voltage Regulator")
      (fields (field (name "PUBLISHER") "Altium Limited"))
      (libsource (lib "ST Power Mgt Voltage Regulator") (part "L7805CD2T"))
    )
    (comp (ref "U6")
      (value "L7805")
      (footprint "TO220")
      (description "Positive Voltage Regulator")
      (fields (field (name "PUBLISHER") "Altium Limited"))
      (libsource (lib "ST Power Mgt Voltage Regulator") (part "L7805CD2T"))
    )
    (comp (ref "U7") (value "ADS1115") (footprint "TSSOP10_N") (libsource (lib "Library") (part "ADS1115")))
    (comp (ref "U8")
      (value "LM1117T-ADJ")
      (footprint "DPAK")
      (description "800mA Low-Dropout Linear Regulator")
      (fields
        (field (name "MANUFACTURER") "National Semiconductor")
        (field (name "DIGIKEYPARTNUMBER") "LM1117T-ADJ-ND")
        (field (name "PUBLISHER") "Altium Limited")
      )
      (libsource (lib "NSC LDO") (part "LM1117T-ADJ"))
    )
    (comp (ref "U9") (value "HMC1001") (footprint "HMC1001") (libsource (lib "Library") (part "HMC1001")))
    (comp (ref "U10")
      (value "LMC7660IM")
      (footprint "sop8")
      (description "Switched Capacitor Voltage Converter")
      (fields
        (field (name "MANUFACTURER") "National Semiconductor")
        (field (name "DIGIKEYPARTNUMBER") "LMC7660IM-ND")
        (field (name "PUBLISHER") "Altium Limited")
      )
      (libsource (lib "NSC Switch Caps") (part "LMC7660IM"))
    )
    (comp (ref "U11")
      (value "AMP04")
      (footprint "sop8")
      (fields (field (name "PUBLISHER") "Altium Limited"))
      (libsource (lib "Miscellaneous Devices") (part "Op Amp"))
    )
    (comp (ref "U12")
      (value "LM4040")
      (footprint "sot-23")
      (description "Precision Micropower Shunt Voltage Reference, 3-pin SOT-23")
      (fields
        (field (name "PARTNUMBER") "LM4040DIM3-10.0")
        (field (name "MANUFACTURER") "National Semiconductor")
        (field (name "PUBLISHER") "Altium Limited")
      )
      (libsource (lib "final_sensor_sch_lib") (part "LM4040"))
    )
  )
  (nets
    (net (code "1") (name "-5V0") (class "Default")
      (node (ref "C35") (pin "2") (pinfunction "2_2") (pintype "passive"))
      (node (ref "R57") (pin "1") (pinfunction "1_1") (pintype "passive"))
      (node (ref "U10") (pin "5") (pinfunction "OUT_5") (pintype "power_in"))
    )
    (net (code "2") (name "/ADS0") (class "Default")
      (node (ref "C39") (pin "1") (pinfunction "1_1") (pintype "passive"))
      (node (ref "R38") (pin "1") (pinfunction "1_1") (pintype "passive"))
      (node (ref "U11") (pin "6") (pinfunction "OUT_6") (pintype "output"))
    )
    (net (code "3") (name "/ADS_ALERT") (class "Default")
      (node (ref "R37") (pin "2") (pinfunction "2_2") (pintype "passive"))
      (node (ref "U7") (pin "2") (pinfunction "ALERT/RDY_2") (pintype "passive"))
    )
    (net (code "4") (name "/IN_RESET") (class "Default")
      (node (ref "Q7") (pin "3") (pinfunction "C_3") (pintype "passive"))
      (node (ref "R19") (pin "1") (pinfunction "1_1") (pintype "passive"))
      (node (ref "U3") (pin "2") (pinfunction "IN_A_2") (pintype "passive"))
    )
    (net (code "5") (name "/IN_SET") (class "Default")
      (node (ref "Q8") (pin "3") (pinfunction "C_3") (pintype "passive"))
      (node (ref "R28") (pin "1") (pinfunction "1_1") (pintype "passive"))
      (node (ref "U3") (pin "4") (pinfunction "IN_B_4") (pintype "passive"))
    )
    (net (code "6") (name "/MICRO_ADC") (class "Default")
      (node (ref "R49") (pin "1") (pinfunction "1_1") (pintype "passive"))
      (node (ref "U9") (pin "7") (pinfunction "Vbridge_7") (pintype "passive"))
    )
    (net (code "7") (name "/N_CURRENT") (class "Default")
      (node (ref "P1") (pin "10") (pinfunction "10_10") (pintype "passive"))
      (node (ref "R6") (pin "2") (pinfunction "2_2") (pintype "passive"))
      (node (ref "R9") (pin "2") (pinfunction "2_2") (pintype "passive"))
    )
    (net (code "8") (name "/OFFSET+") (class "Default")
      (node (ref "R10") (pin "2") (pinfunction "2_2") (pintype "passive"))
      (node (ref "R14") (pin "2") (pinfunction "2_2") (pintype "passive"))
      (node (ref "R47") (pin "2") (pinfunction "2_2") (pintype "passive"))
      (node (ref "R48") (pin "2") (pinfunction "2_2") (pintype "passive"))
      (node (ref "U9") (pin "2") (pinfunction "OFFSET+_2") (pintype "passive"))
    )
    (net (code "9") (name "/OFFSET-") (class "Default")
      (node (ref "Q2") (pin "3") (pinfunction "C_3") (pintype "passive"))
      (node (ref "R16") (pin "2") (pinfunction "2_2") (pintype "passive"))
      (node (ref "R47") (pin "1") (pinfunction "1_1") (pintype "passive"))
      (node (ref "R48") (pin "1") (pinfunction "1_1") (pintype "passive"))
      (node (ref "U9") (pin "6") (pinfunction "OFFSET-_6") (pintype "passive"))
    )
    (net (code "10") (name "/OUT_N") (class "Default")
      (node (ref "R55") (pin "2") (pinfunction "2_2") (pintype "passive"))
      (node (ref "U11") (pin "2") (pinfunction "IN-_2") (pintype "input"))
      (node (ref "U9") (pin "8") (pinfunction "Out-_8") (pintype "passive"))
    )
    (net (code "11") (name "/OUT_P") (class "Default")
      (node (ref "R53") (pin "2") (pinfunction "2_2") (pintype "passive"))
      (node (ref "U11") (pin "3") (pinfunction "IN+_3") (pintype "input"))
      (node (ref "U9") (pin "5") (pinfunction "Out+_5") (pintype "passive"))
    )
    (net (code "12") (name "/OUT_RESET") (class "Default")
      (node (ref "R20") (pin "2") (pinfunction "2_2") (pintype "passive"))
      (node (ref "U3") (pin "7") (pinfunction "OUT_~{B}_7") (pintype "passive"))
    )
    (net (code "13") (name "/OUT_SET") (class "Default")
      (node (ref "R29") (pin "2") (pinfunction "2_2") (pintype "passive"))
      (node (ref "U3") (pin "5") (pinfunction "OUT_B_5") (pintype "passive"))
    )
    (net (code "14") (name "/P_CURRENT") (class "Default")
      (node (ref "P1") (pin "8") (pinfunction "8_8") (pintype "passive"))
      (node (ref "R5") (pin "2") (pinfunction "2_2") (pintype "passive"))
      (node (ref "R8") (pin "2") (pinfunction "2_2") (pintype "passive"))
    )
    (net (code "15") (name "/RESET") (class "Default")
      (node (ref "P1") (pin "3") (pinfunction "3_3") (pintype "passive"))
      (node (ref "R23") (pin "1") (pinfunction "1_1") (pintype "passive"))
    )
    (net (code "16") (name "/SCL") (class "Default")
      (node (ref "P1") (pin "6") (pinfunction "6_6") (pintype "passive"))
      (node (ref "R34") (pin "2") (pinfunction "2_2") (pintype "passive"))
      (node (ref "U7") (pin "10") (pinfunction "SCL_10") (pintype "passive"))
    )
    (net (code "17") (name "/SDA") (class "Default")
      (node (ref "P1") (pin "7") (pinfunction "7_7") (pintype "passive"))
      (node (ref "R35") (pin "2") (pinfunction "2_2") (pintype "passive"))
      (node (ref "U7") (pin "9") (pinfunction "SDA_9") (pintype "passive"))
    )
    (net (code "18") (name "/SET") (class "Default")
      (node (ref "P1") (pin "5") (pinfunction "5_5") (pintype "passive"))
      (node (ref "R30") (pin "1") (pinfunction "1_1") (pintype "passive"))
    )
    (net (code "19") (name "/SR+") (class "Default")
      (node (ref "C6") (pin "2") (pinfunction "2_2") (pintype "passive"))
      (node (ref "C7") (pin "2") (pinfunction "2_2") (pintype "passive"))
      (node (ref "C9") (pin "2") (pinfunction "2_2") (pintype "passive"))
      (node (ref "R27") (pin "1") (pinfunction "1_1") (pintype "passive"))
      (node (ref "U9") (pin "1") (pinfunction "S/R+_1") (pintype "passive"))
    )
    (net (code "20") (name "5V0H") (class "Default")
      (node (ref "C17") (pin "2") (pinfunction "2_2") (pintype "passive"))
      (node (ref "C18") (pin "2") (pinfunction "2_2") (pintype "passive"))
      (node (ref "C19") (pin "1") (pinfunction "1_1") (pintype "passive"))
      (node (ref "C29") (pin "2") (pinfunction "2_2") (pintype "passive"))
      (node (ref "C37") (pin "2") (pinfunction "2_2") (pintype "passive"))
      (node (ref "C38") (pin "2") (pinfunction "2_2") (pintype "passive"))
      (node (ref "C40") (pin "2") (pinfunction "2_2") (pintype "passive"))
      (node (ref "D2") (pin "1") (pinfunction "A_1") (pintype "passive"))
      (node (ref "D3") (pin "2") (pinfunction "K_2") (pintype "passive"))
      (node (ref "F1") (pin "2") (pinfunction "2_2") (pintype "passive"))
      (node (ref "R49") (pin "2") (pinfunction "2_2") (pintype "passive"))
      (node (ref "R5") (pin "1") (pinfunction "1_1") (pintype "passive"))
      (node (ref "R50") (pin "1") (pinfunction "1_1") (pintype "passive"))
      (node (ref "R51") (pin "2") (pinfunction "2_2") (pintype "passive"))
      (node (ref "R6") (pin "1") (pinfunction "1_1") (pintype "passive"))
      (node (ref "U10") (pin "8") (pinfunction "V+_8") (pintype "power_in"))
      (node (ref "U11") (pin "7") (pinfunction "V+_7") (pintype "power_in"))
      (node (ref "U5") (pin "3") (pinfunction "OUT_3") (pintype "power_in"))
    )
    (net (code "21") (name "5V0O") (class "Default")
      (node (ref "C1") (pin "2") (pinfunction "2_2") (pintype "passive"))
      (node (ref "C22") (pin "2") (pinfunction "2_2") (pintype "passive"))
      (node (ref "C23") (pin "2") (pinfunction "2_2") (pintype "passive"))
      (node (ref "C24") (pin "1") (pinfunction "1_1") (pintype "passive"))
      (node (ref "C25") (pin "1") (pinfunction "1_1") (pintype "passive"))
      (node (ref "D4") (pin "1") (pinfunction "A_1") (pintype "passive"))
      (node (ref "D5") (pin "2") (pinfunction "K_2") (pintype "passive"))
      (node (ref "Q5") (pin "2") (pinfunction "C_2") (pintype "passive"))
      (node (ref "Q6") (pin "2") (pinfunction "D_2") (pintype "passive"))
      (node (ref "R22") (pin "3") (pinfunction "BOT_3") (pintype "passive"))
      (node (ref "U1") (pin "8") (pinfunction "V+_8") (pintype "power_in"))
      (node (ref "U6") (pin "3") (pinfunction "OUT_3") (pintype "power_in"))
    )
    (net (code "22") (name "9V0") (class "Default")
      (node (ref "C15") (pin "2") (pinfunction "2_2") (pintype "passive"))
      (node (ref "C16") (pin "2") (pinfunction "2_2") (pintype "passive"))
      (node (ref "D1") (pin "1") (pinfunction "A_1") (pintype "passive"))
      (node (ref "D2") (pin "2") (pinfunction "K_2") (pintype "passive"))
      (node (ref "P1") (pin "2") (pinfunction "2_2") (pintype "passive"))
      (node (ref "R32") (pin "2") (pinfunction "2_2") (pintype "passive"))
      (node (ref "U4") (pin "3") (pinfunction "OUT_3") (pintype "power_in"))
      (node (ref "U5") (pin "1") (pinfunction "IN_1") (pintype "power_in"))
    )
    (net (code "23") (name "11V3") (class "Default")
      (node (ref "C10") (pin "1") (pinfunction "1_1") (pintype "passive"))
      (node (ref "C11") (pin "1") (pinfunction "1_1") (pintype "passive"))
      (node (ref "C33") (pin "2") (pinfunction "2_2") (pintype "passive"))
      (node (ref "F3") (pin "2") (pinfunction "2_2") (pintype "passive"))
      (node (ref "R19") (pin "2") (pinfunction "2_2") (pintype "passive"))
      (node (ref "R26") (pin "1") (pinfunction "1_1") (pintype "passive"))
      (node (ref "R28") (pin "2") (pinfunction "2_2") (pintype "passive"))
      (node (ref "U3") (pin "6") (pinfunction "VDD_6") (pintype "passive"))
    )
    (net (code "24") (name "ADS_VCC") (class "Default")
      (node (ref "C26") (pin "2") (pinfunction "2_2") (pintype "passive"))
      (node (ref "C27") (pin "1") (pinfunction "1_1") (pintype "passive"))
      (node (ref "C28") (pin "2") (pinfunction "2_2") (pintype "passive"))
      (node (ref "F1") (pin "1") (pinfunction "1_1") (pintype "passive"))
      (node (ref "R34") (pin "1") (pinfunction "1_1") (pintype "passive"))
      (node (ref "R35") (pin "1") (pinfunction "1_1") (pintype "passive"))
      (node (ref "R39") (pin "2") (pinfunction "2_2") (pintype "passive"))
      (node (ref "R41") (pin "2") (pinfunction "2_2") (pintype "passive"))
      (node (ref "R43") (pin "2") (pinfunction "2_2") (pintype "passive"))
      (node (ref "U7") (pin "8") (pinfunction "VDD_8") (pintype "passive"))
    )
    (net (code "25") (name "AMP04-") (class "Default")
      (node (ref "C40") (pin "1") (pinfunction "1_1") (pintype "passive"))
      (node (ref "R56") (pin "2") (pinfunction "2_2") (pintype "passive"))
      (node (ref "R57") (pin "2") (pinfunction "2_2") (pintype "passive"))
      (node (ref "U11") (pin "4") (pinfunction "V-_4") (pintype "power_in"))
    )
    (net (code "26") (name "GNDA") (class "Default")
      (node (ref "C1") (pin "1") (pinfunction "1_1") (pintype "passive"))
      (node (ref "C12") (pin "2") (pinfunction "2_2") (pintype "passive"))
      (node (ref "C13") (pin "1") (pinfunction "1_1") (pintype "passive"))
      (node (ref "C14") (pin "1") (pinfunction "1_1") (pintype "passive"))
      (node (ref "C15") (pin "1") (pinfunction "1_1") (pintype "passive"))
      (node (ref "C16") (pin "1") (pinfunction "1_1") (pintype "passive"))
      (node (ref "C17") (pin "1") (pinfunction "1_1") (pintype "passive"))
      (node (ref "C18") (pin "1") (pinfunction "1_1") (pintype "passive"))
      (node (ref "C19") (pin "2") (pinfunction "2_2") (pintype "passive"))
      (node (ref "C2") (pin "2") (pinfunction "2_2") (pintype "passive"))
      (node (ref "C20") (pin "1") (pinfunction "1_1") (pintype "passive"))
      (node (ref "C21") (pin "1") (pinfunction "1_1") (pintype "passive"))
      (node (ref "C22") (pin "1") (pinfunction "1_1") (pintype "passive"))
      (node (ref "C23") (pin "1") (pinfunction "1_1") (pintype "passive"))
      (node (ref "C24") (pin "2") (pinfunction "2_2") (pintype "passive"))
      (node (ref "C25") (pin "2") (pinfunction "2_2") (pintype "passive"))
      (node (ref "C29") (pin "1") (pinfunction "1_1") (pintype "passive"))
      (node (ref "C3") (pin "2") (pinfunction "2_2") (pintype "passive"))
      (node (ref "C35") (pin "1") (pinfunction "1_1") (pintype "passive"))
      (node (ref "C37") (pin "1") (pinfunction "1_1") (pintype "passive"))
      (node (ref "C38") (pin "1") (pinfunction "1_1") (pintype "passive"))
      (node (ref "C4") (pin "2") (pinfunction "2_2") (pintype "passive"))
      (node (ref "C5") (pin "2") (pinfunction "2_2") (pintype "passive"))
      (node (ref "D3") (pin "1") (pinfunction "A_1") (pintype "passive"))
      (node (ref "D5") (pin "1") (pinfunction "A_1") (pintype "passive"))
      (node (ref "F2") (pin "2") (pinfunction "2_2") (pintype "passive"))
      (node (ref "P1") (pin "9") (pinfunction "9_9") (pintype "passive"))
      (node (ref "Q3") (pin "2") (pinfunction "E_2") (pintype "passive"))
      (node (ref "Q4") (pin "2") (pinfunction "E_2") (pintype "passive"))
      (node (ref "R12") (pin "2") (pinfunction "2_2") (pintype "passive"))
      (node (ref "R13") (pin "2") (pinfunction "2_2") (pintype "passive"))
      (node (ref "R15") (pin "1") (pinfunction "1_1") (pintype "passive"))
      (node (ref "R16") (pin "1") (pinfunction "1_1") (pintype "passive"))
      (node (ref "R17") (pin "1") (pinfunction "1_1") (pintype "passive"))
      (node (ref "R22") (pin "1") (pinfunction "TOP_1") (pintype "passive"))
      (node (ref "R24") (pin "2") (pinfunction "2_2") (pintype "passive"))
      (node (ref "R52") (pin "3") (pinfunction "BOT_3") (pintype "passive"))
      (node (ref "R55") (pin "1") (pinfunction "1_1") (pintype "passive"))
      (node (ref "R56") (pin "1") (pinfunction "1_1") (pintype "passive"))
      (node (ref "U1") (pin "4") (pinfunction "V-_4") (pintype "power_in"))
      (node (ref "U10") (pin "3") (pinfunction "GND_3") (pintype "power_in"))
      (node (ref "U12") (pin "2") (pinfunction "-V_2") (pintype "passive"))
      (node (ref "U4") (pin "2") (pinfunction "GND_2") (pintype "power_in"))
      (node (ref "U5") (pin "2") (pinfunction "GND_2") (pintype "power_in"))
      (node (ref "U6") (pin "2") (pinfunction "GND_2") (pintype "power_in"))
      (node (ref "U9") (pin "4") (pinfunction "GND_4") (pintype "passive"))
    )
    (net (code "27") (name "GNDD") (class "Default")
      (node (ref "C10") (pin "2") (pinfunction "2_2") (pintype "passive"))
      (node (ref "C11") (pin "2") (pinfunction "2_2") (pintype "passive"))
      (node (ref "C31") (pin "2") (pinfunction "2_2") (pintype "passive"))
      (node (ref "C32") (pin "1") (pinfunction "1_1") (pintype "passive"))
      (node (ref "C33") (pin "1") (pinfunction "1_1") (pintype "passive"))
      (node (ref "C34") (pin "1") (pinfunction "1_1") (pintype "passive"))
      (node (ref "C8") (pin "2") (pinfunction "2_2") (pintype "passive"))
      (node (ref "P1") (pin "4") (pinfunction "4_4") (pintype "passive"))
      (node (ref "Q7") (pin "2") (pinfunction "E_2") (pintype "passive"))
      (node (ref "Q8") (pin "2") (pinfunction "E_2") (pintype "passive"))
      (node (ref "R25") (pin "1") (pinfunction "1_1") (pintype "passive"))
      (node (ref "R27") (pin "2") (pinfunction "2_2") (pintype "passive"))
      (node (ref "R31") (pin "1") (pinfunction "1_1") (pintype "passive"))
      (node (ref "R46") (pin "1") (pinfunction "1_1") (pintype "passive"))
      (node (ref "U2") (pin "1") (pinfunction "S1_1") (pintype "passive"))
      (node (ref "U3") (pin "3") (pinfunction "GND_3") (pintype "passive"))
      (node (ref "U9") (pin "3") (pinfunction "S/R-_3") (pintype "passive"))
    )
    (net (code "28") (name "GND_ADS") (class "Default")
      (node (ref "C26") (pin "1") (pinfunction "1_1") (pintype "passive"))
      (node (ref "C27") (pin "2") (pinfunction "2_2") (pintype "passive"))
      (node (ref "C28") (pin "1") (pinfunction "1_1") (pintype "passive"))
      (node (ref "C30") (pin "2") (pinfunction "2_2") (pintype "passive"))
      (node (ref "F2") (pin "1") (pinfunction "1_1") (pintype "passive"))
      (node (ref "R36") (pin "1") (pinfunction "1_1") (pintype "passive"))
      (node (ref "R37") (pin "1") (pinfunction "1_1") (pintype "passive"))
      (node (ref "R40") (pin "2") (pinfunction "2_2") (pintype "passive"))
      (node (ref "R42") (pin "2") (pinfunction "2_2") (pintype "passive"))
      (node (ref "R44") (pin "2") (pinfunction "2_2") (pintype "passive"))
      (node (ref "U7") (pin "3") (pinfunction "GND_3") (pintype "passive"))
    )
    (net (code "29") (name "Net-(C6-Pad1)") (class "Default")
      (node (ref "C6") (pin "1") (pinfunction "1_1") (pintype "passive"))
      (node (ref "C7") (pin "1") (pinfunction "1_1") (pintype "passive"))
      (node (ref "C9") (pin "1") (pinfunction "1_1") (pintype "passive"))
      (node (ref "U2") (pin "5") (pinfunction "D2_5") (pintype "passive"))
      (node (ref "U2") (pin "6") (pinfunction "D2_6") (pintype "passive"))
      (node (ref "U2") (pin "7") (pinfunction "D1_7") (pintype "passive"))
      (node (ref "U2") (pin "8") (pinfunction "D1_8") (pintype "passive"))
    )
    (net (code "30") (name "Net-(D4-K)") (class "Default")
      (node (ref "C20") (pin "2") (pinfunction "2_2") (pintype "passive"))
      (node (ref "C21") (pin "2") (pinfunction "2_2") (pintype "passive"))
      (node (ref "D4") (pin "2") (pinfunction "K_2") (pintype "passive"))
      (node (ref "R32") (pin "1") (pinfunction "1_1") (pintype "passive"))
      (node (ref "R33") (pin "1") (pinfunction "1_1") (pintype "passive"))
      (node (ref "U6") (pin "1") (pinfunction "IN_1") (pintype "power_in"))
    )
    (net (code "31") (name "Net-(Q1-B)") (class "Default")
      (node (ref "Q1") (pin "1") (pinfunction "B_1") (pintype "passive"))
      (node (ref "R1") (pin "1") (pinfunction "1_1") (pintype "passive"))
      (node (ref "R3") (pin "1") (pinfunction "1_1") (pintype "passive"))
    )
    (net (code "32") (name "Net-(Q1-C)") (class "Default")
      (node (ref "Q1") (pin "3") (pinfunction "C_3") (pintype "passive"))
      (node (ref "R11") (pin "1") (pinfunction "1_1") (pintype "passive"))
      (node (ref "R15") (pin "2") (pinfunction "2_2") (pintype "passive"))
      (node (ref "R7") (pin "1") (pinfunction "1_1") (pintype "passive"))
    )
    (net (code "33") (name "Net-(Q2-B)") (class "Default")
      (node (ref "Q2") (pin "1") (pinfunction "B_1") (pintype "passive"))
      (node (ref "R2") (pin "1") (pinfunction "1_1") (pintype "passive"))
      (node (ref "R4") (pin "1") (pinfunction "1_1") (pintype "passive"))
    )
    (net (code "34") (name "Net-(Q3-B)") (class "Default")
      (node (ref "Q3") (pin "1") (pinfunction "B_1") (pintype "passive"))
      (node (ref "R12") (pin "1") (pinfunction "1_1") (pintype "passive"))
      (node (ref "R8") (pin "1") (pinfunction "1_1") (pintype "passive"))
    )
    (net (code "35") (name "Net-(Q3-C)") (class "Default")
      (node (ref "Q3") (pin "3") (pinfunction "C_3") (pintype "passive"))
      (node (ref "R3") (pin "2") (pinfunction "2_2") (pintype "passive"))
    )
    (net (code "36") (name "Net-(Q4-B)") (class "Default")
      (node (ref "Q4") (pin "1") (pinfunction "B_1") (pintype "passive"))
      (node (ref "R13") (pin "1") (pinfunction "1_1") (pintype "passive"))
      (node (ref "R9") (pin "1") (pinfunction "1_1") (pintype "passive"))
    )
    (net (code "37") (name "Net-(Q4-C)") (class "Default")
      (node (ref "Q4") (pin "3") (pinfunction "C_3") (pintype "passive"))
      (node (ref "R4") (pin "2") (pinfunction "2_2") (pintype "passive"))
    )
    (net (code "38") (name "Net-(Q5-B)") (class "Default")
      (node (ref "Q5") (pin "1") (pinfunction "B_1") (pintype "passive"))
      (node (ref "Q6") (pin "1") (pinfunction "G_1") (pintype "passive"))
      (node (ref "U1") (pin "7") (pinfunction "OUT_7") (pintype "output"))
    )
    (net (code "39") (name "Net-(Q7-B)") (class "Default")
      (node (ref "Q7") (pin "1") (pinfunction "B_1") (pintype "passive"))
      (node (ref "R23") (pin "2") (pinfunction "2_2") (pintype "passive"))
      (node (ref "R25") (pin "2") (pinfunction "2_2") (pintype "passive"))
    )
    (net (code "40") (name "Net-(Q8-B)") (class "Default")
      (node (ref "Q8") (pin "1") (pinfunction "B_1") (pintype "passive"))
      (node (ref "R30") (pin "2") (pinfunction "2_2") (pintype "passive"))
      (node (ref "R31") (pin "2") (pinfunction "2_2") (pintype "passive"))
    )
    (net (code "41") (name "Net-(R10-Pad1)") (class "Default")
      (node (ref "R10") (pin "1") (pinfunction "1_1") (pintype "passive"))
      (node (ref "R11") (pin "2") (pinfunction "2_2") (pintype "passive"))
      (node (ref "R14") (pin "1") (pinfunction "1_1") (pintype "passive"))
      (node (ref "R7") (pin "2") (pinfunction "2_2") (pintype "passive"))
    )
    (net (code "42") (name "Net-(R22-TAP)") (class "Default")
      (node (ref "R21") (pin "1") (pinfunction "1_1") (pintype "passive"))
      (node (ref "R22") (pin "2") (pinfunction "TAP_2") (pintype "passive"))
    )
    (net (code "43") (name "Net-(R52-TAP)") (class "Default")
      (node (ref "R50") (pin "2") (pinfunction "2_2") (pintype "passive"))
      (node (ref "R52") (pin "1") (pinfunction "TOP_1") (pintype "passive"))
      (node (ref "R52") (pin "2") (pinfunction "TAP_2") (pintype "passive"))
      (node (ref "R53") (pin "1") (pinfunction "1_1") (pintype "passive"))
    )
    (net (code "44") (name "Net-(R54-Pad2)") (class "Default")
      (node (ref "R54") (pin "2") (pinfunction "2_2") (pintype "passive"))
      (node (ref "U11") (pin "1") (pinfunction "OS_NUL_1") (pintype "passive"))
    )
    (net (code "45") (name "Net-(U1B-IN+)") (class "Default")
      (node (ref "C2") (pin "1") (pinfunction "1_1") (pintype "passive"))
      (node (ref "C3") (pin "1") (pinfunction "1_1") (pintype "passive"))
      (node (ref "R21") (pin "2") (pinfunction "2_2") (pintype "passive"))
      (node (ref "R24") (pin "1") (pinfunction "1_1") (pintype "passive"))
      (node (ref "U1") (pin "5") (pinfunction "IN+_5") (pintype "input"))
    )
    (net (code "46") (name "Net-(U1B-IN-)") (class "Default")
      (node (ref "R17") (pin "2") (pinfunction "2_2") (pintype "passive"))
      (node (ref "R18") (pin "1") (pinfunction "1_1") (pintype "passive"))
      (node (ref "U1") (pin "6") (pinfunction "IN-_6") (pintype "input"))
    )
    (net (code "47") (name "Net-(U2-G1)") (class "Default")
      (node (ref "R20") (pin "1") (pinfunction "1_1") (pintype "passive"))
      (node (ref "U2") (pin "2") (pinfunction "G1_2") (pintype "passive"))
    )
    (net (code "48") (name "Net-(U2-G2)") (class "Default")
      (node (ref "R29") (pin "1") (pinfunction "1_1") (pintype "passive"))
      (node (ref "U2") (pin "4") (pinfunction "G2_4") (pintype "passive"))
    )
    (net (code "49") (name "Net-(U2-S2)") (class "Default")
      (node (ref "C8") (pin "1") (pinfunction "1_1") (pintype "passive"))
      (node (ref "R26") (pin "2") (pinfunction "2_2") (pintype "passive"))
      (node (ref "U2") (pin "3") (pinfunction "S2_3") (pintype "passive"))
    )
    (net (code "50") (name "Net-(U7-A0)") (class "Default")
      (node (ref "C30") (pin "1") (pinfunction "1_1") (pintype "passive"))
      (node (ref "R38") (pin "2") (pinfunction "2_2") (pintype "passive"))
      (node (ref "U7") (pin "4") (pinfunction "A0_4") (pintype "passive"))
    )
    (net (code "51") (name "Net-(U7-A1)") (class "Default")
      (node (ref "R39") (pin "1") (pinfunction "1_1") (pintype "passive"))
      (node (ref "R40") (pin "1") (pinfunction "1_1") (pintype "passive"))
      (node (ref "U7") (pin "5") (pinfunction "A1_5") (pintype "passive"))
    )
    (net (code "52") (name "Net-(U7-A2)") (class "Default")
      (node (ref "R41") (pin "1") (pinfunction "1_1") (pintype "passive"))
      (node (ref "R42") (pin "1") (pinfunction "1_1") (pintype "passive"))
      (node (ref "U7") (pin "6") (pinfunction "A2_6") (pintype "passive"))
    )
    (net (code "53") (name "Net-(U7-A3)") (class "Default")
      (node (ref "R43") (pin "1") (pinfunction "1_1") (pintype "passive"))
      (node (ref "R44") (pin "1") (pinfunction "1_1") (pintype "passive"))
      (node (ref "U7") (pin "7") (pinfunction "A3_7") (pintype "passive"))
    )
    (net (code "54") (name "Net-(U7-ADDR)") (class "Default")
      (node (ref "R36") (pin "2") (pinfunction "2_2") (pintype "passive"))
      (node (ref "U7") (pin "1") (pinfunction "ADDR_1") (pintype "passive"))
    )
    (net (code "55") (name "Net-(U8-ADJ)") (class "Default")
      (node (ref "R45") (pin "1") (pinfunction "1_1") (pintype "passive"))
      (node (ref "R46") (pin "2") (pinfunction "2_2") (pintype "passive"))
      (node (ref "U8") (pin "1") (pinfunction "ADJ_1") (pintype "input"))
    )
    (net (code "56") (name "Net-(U8-OUT)") (class "Default")
      (node (ref "C31") (pin "1") (pinfunction "1_1") (pintype "passive"))
      (node (ref "C32") (pin "2") (pinfunction "2_2") (pintype "passive"))
      (node (ref "F3") (pin "1") (pinfunction "1_1") (pintype "passive"))
      (node (ref "R45") (pin "2") (pinfunction "2_2") (pintype "passive"))
      (node (ref "U8") (pin "2") (pinfunction "OUT_2") (pintype "power_in"))
    )
    (net (code "57") (name "Net-(U10-C1+)") (class "Default")
      (node (ref "C36") (pin "1") (pinfunction "1_1") (pintype "passive"))
      (node (ref "U10") (pin "2") (pinfunction "C1+_2") (pintype "input"))
    )
    (net (code "58") (name "Net-(U10-C1-)") (class "Default")
      (node (ref "C36") (pin "2") (pinfunction "2_2") (pintype "passive"))
      (node (ref "U10") (pin "4") (pinfunction "C1-_4") (pintype "input"))
    )
    (net (code "59") (name "Net-(U11-TAB)") (class "Default")
      (node (ref "C39") (pin "2") (pinfunction "2_2") (pintype "passive"))
      (node (ref "R54") (pin "1") (pinfunction "1_1") (pintype "passive"))
      (node (ref "U11") (pin "8") (pinfunction "TAB_8") (pintype "passive"))
    )
    (net (code "60") (name "Net-(U12-+V)") (class "Default")
      (node (ref "R51") (pin "1") (pinfunction "1_1") (pintype "passive"))
      (node (ref "U11") (pin "5") (pinfunction "OS_NUL_5") (pintype "passive"))
      (node (ref "U12") (pin "1") (pinfunction "+V_1") (pintype "passive"))
    )
    (net (code "61") (name "OP_OUT") (class "Default")
      (node (ref "C4") (pin "1") (pinfunction "1_1") (pintype "passive"))
      (node (ref "C5") (pin "1") (pinfunction "1_1") (pintype "passive"))
      (node (ref "Q1") (pin "2") (pinfunction "E_2") (pintype "passive"))
      (node (ref "Q2") (pin "2") (pinfunction "E_2") (pintype "passive"))
      (node (ref "Q5") (pin "3") (pinfunction "E_3") (pintype "passive"))
      (node (ref "Q6") (pin "3") (pinfunction "S_3") (pintype "passive"))
      (node (ref "R1") (pin "2") (pinfunction "2_2") (pintype "passive"))
      (node (ref "R18") (pin "2") (pinfunction "2_2") (pintype "passive"))
      (node (ref "R2") (pin "2") (pinfunction "2_2") (pintype "passive"))
    )
    (net (code "62") (name "VCC_IN") (class "Default")
      (node (ref "C12") (pin "1") (pinfunction "1_1") (pintype "passive"))
      (node (ref "C13") (pin "2") (pinfunction "2_2") (pintype "passive"))
      (node (ref "C14") (pin "2") (pinfunction "2_2") (pintype "passive"))
      (node (ref "C34") (pin "2") (pinfunction "2_2") (pintype "passive"))
      (node (ref "D1") (pin "2") (pinfunction "K_2") (pintype "passive"))
      (node (ref "P1") (pin "1") (pinfunction "1_1") (pintype "passive"))
      (node (ref "R33") (pin "2") (pinfunction "2_2") (pintype "passive"))
      (node (ref "U4") (pin "1") (pinfunction "IN_1") (pintype "power_in"))
      (node (ref "U8") (pin "3") (pinfunction "IN_3") (pintype "power_in"))
    )
    (net (code "63") (name "unconnected-(Hole1-Pad1)") (class "Default")
      (node (ref "Hole1") (pin "1") (pinfunction "1_1") (pintype "passive+no_connect"))
    )
    (net (code "64") (name "unconnected-(Hole2-Pad1)") (class "Default")
      (node (ref "Hole2") (pin "1") (pinfunction "1_1") (pintype "passive+no_connect"))
    )
    (net (code "65") (name "unconnected-(Hole3-Pad1)") (class "Default")
      (node (ref "Hole3") (pin "1") (pinfunction "1_1") (pintype "passive+no_connect"))
    )
    (net (code "66") (name "unconnected-(Hole4-Pad1)") (class "Default")
      (node (ref "Hole4") (pin "1") (pinfunction "1_1") (pintype "passive+no_connect"))
    )
    (net (code "67") (name "unconnected-(U1A-IN+-Pad3)") (class "Default")
      (node (ref "U1") (pin "3") (pinfunction "IN+_3") (pintype "input+no_connect"))
    )
    (net (code "68") (name "unconnected-(U1A-IN--Pad2)") (class "Default")
      (node (ref "U1") (pin "2") (pinfunction "IN-_2") (pintype "input+no_connect"))
    )
    (net (code "69") (name "unconnected-(U1A-OUT-Pad1)") (class "Default")
      (node (ref "U1") (pin "1") (pinfunction "OUT_1") (pintype "output+no_connect"))
    )
    (net (code "70") (name "unconnected-(U3-NC-Pad1)") (class "Default")
      (node (ref "U3") (pin "1") (pinfunction "NC_1") (pintype "passive+no_connect"))
    )
    (net (code "71") (name "unconnected-(U3-NC-Pad8)") (class "Default")
      (node (ref "U3") (pin "8") (pinfunction "NC_8") (pintype "passive+no_connect"))
    )
    (net (code "72") (name "unconnected-(U10-LV-Pad6)") (class "Default")
      (node (ref "U10") (pin "6") (pinfunction "LV_6") (pintype "input+no_connect"))
    )
    (net (code "73") (name "unconnected-(U10-NC-Pad1)") (class "Default")
      (node (ref "U10") (pin "1") (pinfunction "NC_1") (pintype "passive+no_connect"))
    )
    (net (code "74") (name "unconnected-(U10-OSC-Pad7)") (class "Default")
      (node (ref "U10") (pin "7") (pinfunction "OSC_7") (pintype "input+no_connect"))
    )
    (net (code "75") (name "unconnected-(U12-NC-Pad3)") (class "Default")
      (node (ref "U12") (pin "3") (pinfunction "NC_3") (pintype "passive+no_connect"))
    )
  )
)
